# flackerlicht.net
KiCad netlist of a schematic drawn in EAGLE
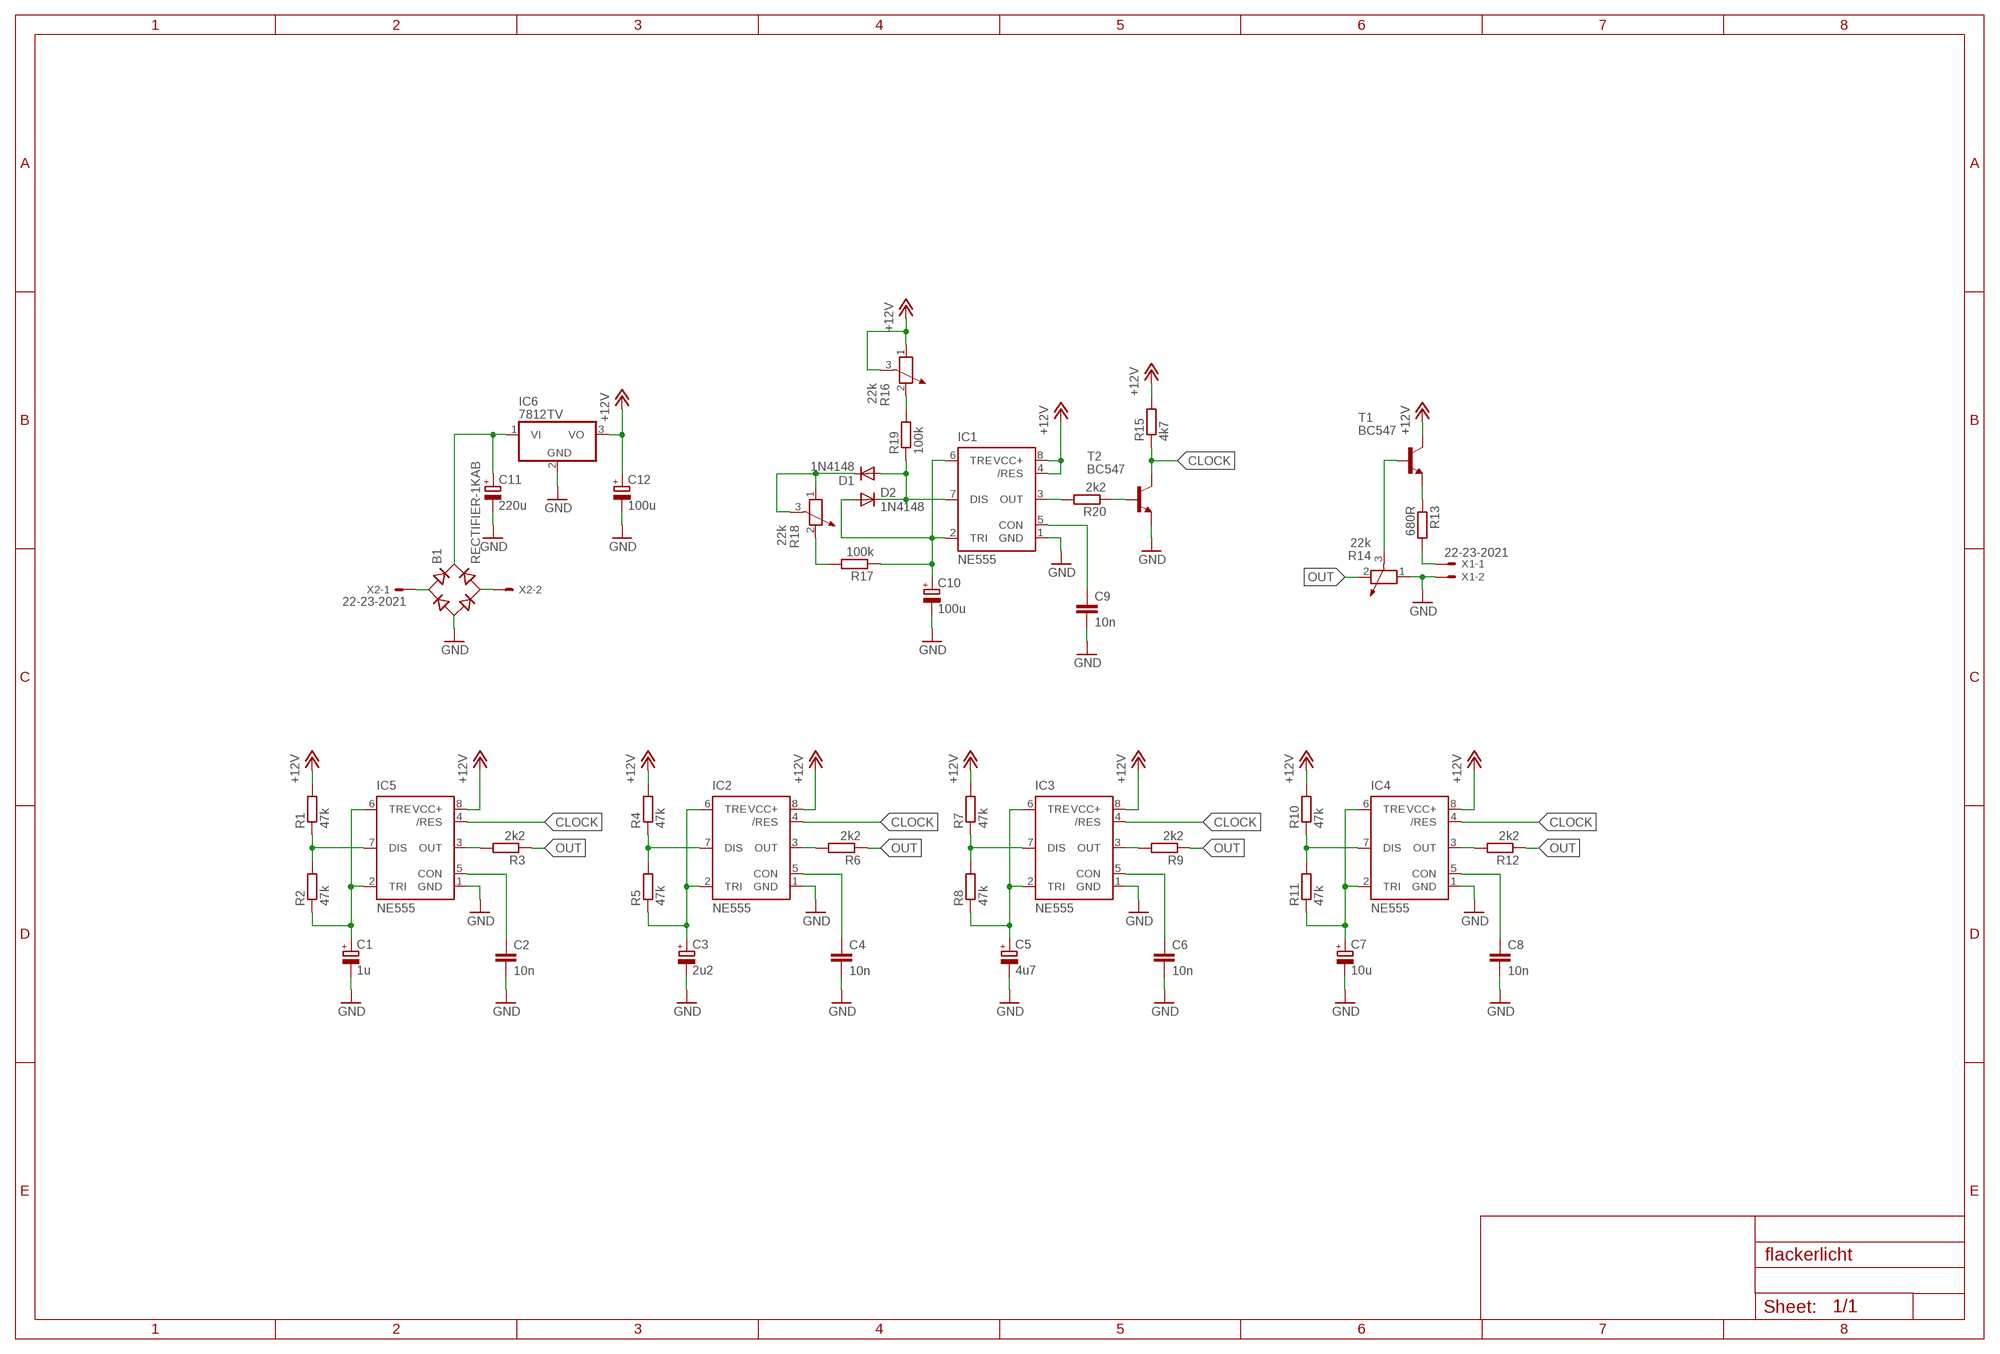
[diagram p0: schematic, sheet 1]

(export (version "E")
  (design (tool "Eeschema 10.0.6"))
  (components
    (comp (ref "B1")
      (value "RECTIFIER-1KAB")
      (footprint "eagle-import:1KAB")
      (libsource (lib "eagle-import") (part "RECTIFIER-1KAB"))
    )
    (comp (ref "C1")
      (value "1u")
      (footprint "eagle-import:E2,5-6")
      (libsource (lib "eagle-import") (part "CPOL-EUE2.5-6"))
    )
    (comp (ref "C2")
      (value "10n")
      (footprint "eagle-import:C050-035X075")
      (libsource (lib "eagle-import") (part "C-EU050-035X075"))
    )
    (comp (ref "C3")
      (value "2u2")
      (footprint "eagle-import:E2,5-6")
      (libsource (lib "eagle-import") (part "CPOL-EUE2.5-6"))
    )
    (comp (ref "C4")
      (value "10n")
      (footprint "eagle-import:C050-035X075")
      (libsource (lib "eagle-import") (part "C-EU050-035X075"))
    )
    (comp (ref "C5")
      (value "4u7")
      (footprint "eagle-import:E2,5-6")
      (libsource (lib "eagle-import") (part "CPOL-EUE2.5-6"))
    )
    (comp (ref "C6")
      (value "10n")
      (footprint "eagle-import:C050-035X075")
      (libsource (lib "eagle-import") (part "C-EU050-035X075"))
    )
    (comp (ref "C7")
      (value "10u")
      (footprint "eagle-import:E2,5-6")
      (libsource (lib "eagle-import") (part "CPOL-EUE2.5-6"))
    )
    (comp (ref "C8")
      (value "10n")
      (footprint "eagle-import:C050-035X075")
      (libsource (lib "eagle-import") (part "C-EU050-035X075"))
    )
    (comp (ref "C9")
      (value "10n")
      (footprint "eagle-import:C050-035X075")
      (libsource (lib "eagle-import") (part "C-EU050-035X075"))
    )
    (comp (ref "C10")
      (value "100u")
      (footprint "eagle-import:E3,5-8")
      (libsource (lib "eagle-import") (part "CPOL-EUE3.5-8"))
    )
    (comp (ref "C11")
      (value "220u")
      (footprint "eagle-import:E3,5-8")
      (libsource (lib "eagle-import") (part "CPOL-EUE3.5-8"))
    )
    (comp (ref "C12")
      (value "100u")
      (footprint "eagle-import:E3,5-8")
      (libsource (lib "eagle-import") (part "CPOL-EUE3.5-8"))
    )
    (comp (ref "D1")
      (value "1N4148")
      (footprint "eagle-import:DO35-10")
      (libsource (lib "eagle-import") (part "1N4148DO35-10"))
    )
    (comp (ref "D2")
      (value "1N4148")
      (footprint "eagle-import:DO35-10")
      (libsource (lib "eagle-import") (part "1N4148DO35-10"))
    )
    (comp (ref "IC1")
      (value "NE555")
      (footprint "eagle-import:DIL-08")
      (fields (field (name "MF") "Arrow Electronics") (field (name "MPN") "NE555N"))
      (libsource (lib "eagle-import") (part "NE555"))
    )
    (comp (ref "IC2")
      (value "NE555")
      (footprint "eagle-import:DIL-08")
      (fields (field (name "MF") "Arrow Electronics") (field (name "MPN") "NE555N"))
      (libsource (lib "eagle-import") (part "NE555"))
    )
    (comp (ref "IC3")
      (value "NE555")
      (footprint "eagle-import:DIL-08")
      (fields (field (name "MF") "Arrow Electronics") (field (name "MPN") "NE555N"))
      (libsource (lib "eagle-import") (part "NE555"))
    )
    (comp (ref "IC4")
      (value "NE555")
      (footprint "eagle-import:DIL-08")
      (fields (field (name "MF") "Arrow Electronics") (field (name "MPN") "NE555N"))
      (libsource (lib "eagle-import") (part "NE555"))
    )
    (comp (ref "IC5")
      (value "NE555")
      (footprint "eagle-import:DIL-08")
      (fields (field (name "MF") "Arrow Electronics") (field (name "MPN") "NE555N"))
      (libsource (lib "eagle-import") (part "NE555"))
    )
    (comp (ref "IC6")
      (value "7812TV")
      (footprint "eagle-import:TO220V")
      (libsource (lib "eagle-import") (part "78TV12"))
    )
    (comp (ref "R1")
      (value "47k")
      (footprint "eagle-import:0309_10")
      (libsource (lib "eagle-import") (part "R-EU_0309/10"))
    )
    (comp (ref "R2")
      (value "47k")
      (footprint "eagle-import:0309_10")
      (libsource (lib "eagle-import") (part "R-EU_0309/10"))
    )
    (comp (ref "R3")
      (value "2k2")
      (footprint "eagle-import:0309_10")
      (libsource (lib "eagle-import") (part "R-EU_0309/10"))
    )
    (comp (ref "R4")
      (value "47k")
      (footprint "eagle-import:0309_10")
      (libsource (lib "eagle-import") (part "R-EU_0309/10"))
    )
    (comp (ref "R5")
      (value "47k")
      (footprint "eagle-import:0309_10")
      (libsource (lib "eagle-import") (part "R-EU_0309/10"))
    )
    (comp (ref "R6")
      (value "2k2")
      (footprint "eagle-import:0309_10")
      (libsource (lib "eagle-import") (part "R-EU_0309/10"))
    )
    (comp (ref "R7")
      (value "47k")
      (footprint "eagle-import:0309_10")
      (libsource (lib "eagle-import") (part "R-EU_0309/10"))
    )
    (comp (ref "R8")
      (value "47k")
      (footprint "eagle-import:0309_10")
      (libsource (lib "eagle-import") (part "R-EU_0309/10"))
    )
    (comp (ref "R9")
      (value "2k2")
      (footprint "eagle-import:0309_10")
      (libsource (lib "eagle-import") (part "R-EU_0309/10"))
    )
    (comp (ref "R10")
      (value "47k")
      (footprint "eagle-import:0309_10")
      (libsource (lib "eagle-import") (part "R-EU_0309/10"))
    )
    (comp (ref "R11")
      (value "47k")
      (footprint "eagle-import:0309_10")
      (libsource (lib "eagle-import") (part "R-EU_0309/10"))
    )
    (comp (ref "R12")
      (value "2k2")
      (footprint "eagle-import:0309_10")
      (libsource (lib "eagle-import") (part "R-EU_0309/10"))
    )
    (comp (ref "R13")
      (value "680R")
      (footprint "eagle-import:0309_10")
      (libsource (lib "eagle-import") (part "R-EU_0309/10"))
    )
    (comp (ref "R14")
      (value "22k")
      (footprint "eagle-import:PT-10")
      (libsource (lib "eagle-import") (part "POTENTIOMETER_PT-10"))
    )
    (comp (ref "R15")
      (value "4k7")
      (footprint "eagle-import:0309_10")
      (libsource (lib "eagle-import") (part "R-EU_0309/10"))
    )
    (comp (ref "R16")
      (value "22k")
      (footprint "eagle-import:PT-10")
      (libsource (lib "eagle-import") (part "POTENTIOMETER_PT-10"))
    )
    (comp (ref "R17")
      (value "100k")
      (footprint "eagle-import:0309_10")
      (libsource (lib "eagle-import") (part "R-EU_0309/10"))
    )
    (comp (ref "R18")
      (value "22k")
      (footprint "eagle-import:PT-10")
      (libsource (lib "eagle-import") (part "POTENTIOMETER_PT-10"))
    )
    (comp (ref "R19")
      (value "100k")
      (footprint "eagle-import:0309_10")
      (libsource (lib "eagle-import") (part "R-EU_0309/10"))
    )
    (comp (ref "R20")
      (value "2k2")
      (footprint "eagle-import:0309_10")
      (libsource (lib "eagle-import") (part "R-EU_0309/10"))
    )
    (comp (ref "T1")
      (value "BC547")
      (footprint "eagle-import:TO92")
      (libsource (lib "eagle-import") (part "BC547"))
    )
    (comp (ref "T2")
      (value "BC547")
      (footprint "eagle-import:TO92")
      (libsource (lib "eagle-import") (part "BC547"))
    )
    (comp (ref "X1")
      (value "22-23-2021")
      (footprint "eagle-import:22-23-2021")
      (fields (field (name "MF") "MOLEX"))
      (libsource (lib "eagle-import") (part "22-23-2021"))
    )
    (comp (ref "X2")
      (value "22-23-2021")
      (footprint "eagle-import:22-23-2021")
      (fields
        (field (name "MF") "MOLEX")
        (field (name "MF_1") "MOLEX")
        (field (name "MPN") "22-23-2021")
        (field (name "OC_FARNELL") "1462926")
        (field (name "OC_NEWARK") "25C3832")
      )
      (libsource (lib "eagle-import") (part "22-23-2021"))
    )
  )
  (nets
    (net (code "1") (name "+12V") (class "Default")
      (node (ref "C12") (pin "+") (pinfunction "+_+") (pintype "passive"))
      (node (ref "IC1") (pin "4") (pinfunction "/RES_4") (pintype "input"))
      (node (ref "IC1") (pin "8") (pinfunction "VCC+_8") (pintype "power_in"))
      (node (ref "IC2") (pin "8") (pinfunction "VCC+_8") (pintype "power_in"))
      (node (ref "IC3") (pin "8") (pinfunction "VCC+_8") (pintype "power_in"))
      (node (ref "IC4") (pin "8") (pinfunction "VCC+_8") (pintype "power_in"))
      (node (ref "IC5") (pin "8") (pinfunction "VCC+_8") (pintype "power_in"))
      (node (ref "IC6") (pin "3") (pinfunction "VO_3") (pintype "passive"))
      (node (ref "R1") (pin "2") (pinfunction "2_2") (pintype "passive"))
      (node (ref "R10") (pin "2") (pinfunction "2_2") (pintype "passive"))
      (node (ref "R15") (pin "2") (pinfunction "2_2") (pintype "passive"))
      (node (ref "R16") (pin "1") (pinfunction "1_1") (pintype "passive"))
      (node (ref "R16") (pin "3") (pinfunction "3_3") (pintype "passive"))
      (node (ref "R4") (pin "2") (pinfunction "2_2") (pintype "passive"))
      (node (ref "R7") (pin "2") (pinfunction "2_2") (pintype "passive"))
      (node (ref "T1") (pin "3") (pinfunction "C_3") (pintype "passive"))
    )
    (net (code "2") (name "CLOCK") (class "Default")
      (node (ref "IC2") (pin "4") (pinfunction "/RES_4") (pintype "input"))
      (node (ref "IC3") (pin "4") (pinfunction "/RES_4") (pintype "input"))
      (node (ref "IC4") (pin "4") (pinfunction "/RES_4") (pintype "input"))
      (node (ref "IC5") (pin "4") (pinfunction "/RES_4") (pintype "input"))
      (node (ref "R15") (pin "1") (pinfunction "1_1") (pintype "passive"))
      (node (ref "T2") (pin "3") (pinfunction "C_3") (pintype "passive"))
    )
    (net (code "3") (name "GND") (class "Default")
      (node (ref "B1") (pin "-") (pinfunction "-_-") (pintype "passive"))
      (node (ref "C1") (pin "-") (pinfunction "-_-") (pintype "passive"))
      (node (ref "C10") (pin "-") (pinfunction "-_-") (pintype "passive"))
      (node (ref "C11") (pin "-") (pinfunction "-_-") (pintype "passive"))
      (node (ref "C12") (pin "-") (pinfunction "-_-") (pintype "passive"))
      (node (ref "C2") (pin "2") (pinfunction "2_2") (pintype "passive"))
      (node (ref "C3") (pin "-") (pinfunction "-_-") (pintype "passive"))
      (node (ref "C4") (pin "2") (pinfunction "2_2") (pintype "passive"))
      (node (ref "C5") (pin "-") (pinfunction "-_-") (pintype "passive"))
      (node (ref "C6") (pin "2") (pinfunction "2_2") (pintype "passive"))
      (node (ref "C7") (pin "-") (pinfunction "-_-") (pintype "passive"))
      (node (ref "C8") (pin "2") (pinfunction "2_2") (pintype "passive"))
      (node (ref "C9") (pin "2") (pinfunction "2_2") (pintype "passive"))
      (node (ref "IC1") (pin "1") (pinfunction "GND_1") (pintype "power_in"))
      (node (ref "IC2") (pin "1") (pinfunction "GND_1") (pintype "power_in"))
      (node (ref "IC3") (pin "1") (pinfunction "GND_1") (pintype "power_in"))
      (node (ref "IC4") (pin "1") (pinfunction "GND_1") (pintype "power_in"))
      (node (ref "IC5") (pin "1") (pinfunction "GND_1") (pintype "power_in"))
      (node (ref "IC6") (pin "2") (pinfunction "GND_2") (pintype "passive"))
      (node (ref "R14") (pin "1") (pinfunction "1_1") (pintype "passive"))
      (node (ref "T2") (pin "1") (pinfunction "E_1") (pintype "passive"))
      (node (ref "X1") (pin "2") (pinfunction "S_2") (pintype "passive"))
    )
    (net (code "4") (name "Net-(D1-PadC)") (class "Default")
      (node (ref "D1") (pin "C") (pinfunction "C_C") (pintype "passive"))
      (node (ref "R18") (pin "1") (pinfunction "1_1") (pintype "passive"))
      (node (ref "R18") (pin "3") (pinfunction "3_3") (pintype "passive"))
    )
    (net (code "5") (name "Net-(IC1-CON)") (class "Default")
      (node (ref "C9") (pin "1") (pinfunction "1_1") (pintype "passive"))
      (node (ref "IC1") (pin "5") (pinfunction "CON_5") (pintype "input"))
    )
    (net (code "6") (name "Net-(IC1-DIS)") (class "Default")
      (node (ref "D1") (pin "A") (pinfunction "A_A") (pintype "passive"))
      (node (ref "D2") (pin "C") (pinfunction "C_C") (pintype "passive"))
      (node (ref "IC1") (pin "7") (pinfunction "DIS_7") (pintype "input"))
      (node (ref "R19") (pin "1") (pinfunction "1_1") (pintype "passive"))
    )
    (net (code "7") (name "Net-(IC1-OUT)") (class "Default")
      (node (ref "IC1") (pin "3") (pinfunction "OUT_3") (pintype "output"))
      (node (ref "R20") (pin "2") (pinfunction "2_2") (pintype "passive"))
    )
    (net (code "8") (name "Net-(IC1-TRE)") (class "Default")
      (node (ref "C10") (pin "+") (pinfunction "+_+") (pintype "passive"))
      (node (ref "D2") (pin "A") (pinfunction "A_A") (pintype "passive"))
      (node (ref "IC1") (pin "2") (pinfunction "TRI_2") (pintype "input"))
      (node (ref "IC1") (pin "6") (pinfunction "TRE_6") (pintype "input"))
      (node (ref "R17") (pin "1") (pinfunction "1_1") (pintype "passive"))
    )
    (net (code "9") (name "Net-(IC2-CON)") (class "Default")
      (node (ref "C4") (pin "1") (pinfunction "1_1") (pintype "passive"))
      (node (ref "IC2") (pin "5") (pinfunction "CON_5") (pintype "input"))
    )
    (net (code "10") (name "Net-(IC2-DIS)") (class "Default")
      (node (ref "IC2") (pin "7") (pinfunction "DIS_7") (pintype "input"))
      (node (ref "R4") (pin "1") (pinfunction "1_1") (pintype "passive"))
      (node (ref "R5") (pin "2") (pinfunction "2_2") (pintype "passive"))
    )
    (net (code "11") (name "Net-(IC2-OUT)") (class "Default")
      (node (ref "IC2") (pin "3") (pinfunction "OUT_3") (pintype "output"))
      (node (ref "R6") (pin "2") (pinfunction "2_2") (pintype "passive"))
    )
    (net (code "12") (name "Net-(IC2-TRE)") (class "Default")
      (node (ref "C3") (pin "+") (pinfunction "+_+") (pintype "passive"))
      (node (ref "IC2") (pin "2") (pinfunction "TRI_2") (pintype "input"))
      (node (ref "IC2") (pin "6") (pinfunction "TRE_6") (pintype "input"))
      (node (ref "R5") (pin "1") (pinfunction "1_1") (pintype "passive"))
    )
    (net (code "13") (name "Net-(IC3-CON)") (class "Default")
      (node (ref "C6") (pin "1") (pinfunction "1_1") (pintype "passive"))
      (node (ref "IC3") (pin "5") (pinfunction "CON_5") (pintype "input"))
    )
    (net (code "14") (name "Net-(IC3-DIS)") (class "Default")
      (node (ref "IC3") (pin "7") (pinfunction "DIS_7") (pintype "input"))
      (node (ref "R7") (pin "1") (pinfunction "1_1") (pintype "passive"))
      (node (ref "R8") (pin "2") (pinfunction "2_2") (pintype "passive"))
    )
    (net (code "15") (name "Net-(IC3-OUT)") (class "Default")
      (node (ref "IC3") (pin "3") (pinfunction "OUT_3") (pintype "output"))
      (node (ref "R9") (pin "2") (pinfunction "2_2") (pintype "passive"))
    )
    (net (code "16") (name "Net-(IC3-TRE)") (class "Default")
      (node (ref "C5") (pin "+") (pinfunction "+_+") (pintype "passive"))
      (node (ref "IC3") (pin "2") (pinfunction "TRI_2") (pintype "input"))
      (node (ref "IC3") (pin "6") (pinfunction "TRE_6") (pintype "input"))
      (node (ref "R8") (pin "1") (pinfunction "1_1") (pintype "passive"))
    )
    (net (code "17") (name "Net-(IC4-CON)") (class "Default")
      (node (ref "C8") (pin "1") (pinfunction "1_1") (pintype "passive"))
      (node (ref "IC4") (pin "5") (pinfunction "CON_5") (pintype "input"))
    )
    (net (code "18") (name "Net-(IC4-DIS)") (class "Default")
      (node (ref "IC4") (pin "7") (pinfunction "DIS_7") (pintype "input"))
      (node (ref "R10") (pin "1") (pinfunction "1_1") (pintype "passive"))
      (node (ref "R11") (pin "2") (pinfunction "2_2") (pintype "passive"))
    )
    (net (code "19") (name "Net-(IC4-OUT)") (class "Default")
      (node (ref "IC4") (pin "3") (pinfunction "OUT_3") (pintype "output"))
      (node (ref "R12") (pin "2") (pinfunction "2_2") (pintype "passive"))
    )
    (net (code "20") (name "Net-(IC4-TRE)") (class "Default")
      (node (ref "C7") (pin "+") (pinfunction "+_+") (pintype "passive"))
      (node (ref "IC4") (pin "2") (pinfunction "TRI_2") (pintype "input"))
      (node (ref "IC4") (pin "6") (pinfunction "TRE_6") (pintype "input"))
      (node (ref "R11") (pin "1") (pinfunction "1_1") (pintype "passive"))
    )
    (net (code "21") (name "Net-(IC5-CON)") (class "Default")
      (node (ref "C2") (pin "1") (pinfunction "1_1") (pintype "passive"))
      (node (ref "IC5") (pin "5") (pinfunction "CON_5") (pintype "input"))
    )
    (net (code "22") (name "Net-(IC5-DIS)") (class "Default")
      (node (ref "IC5") (pin "7") (pinfunction "DIS_7") (pintype "input"))
      (node (ref "R1") (pin "1") (pinfunction "1_1") (pintype "passive"))
      (node (ref "R2") (pin "2") (pinfunction "2_2") (pintype "passive"))
    )
    (net (code "23") (name "Net-(IC5-OUT)") (class "Default")
      (node (ref "IC5") (pin "3") (pinfunction "OUT_3") (pintype "output"))
      (node (ref "R3") (pin "2") (pinfunction "2_2") (pintype "passive"))
    )
    (net (code "24") (name "Net-(IC5-TRE)") (class "Default")
      (node (ref "C1") (pin "+") (pinfunction "+_+") (pintype "passive"))
      (node (ref "IC5") (pin "2") (pinfunction "TRI_2") (pintype "input"))
      (node (ref "IC5") (pin "6") (pinfunction "TRE_6") (pintype "input"))
      (node (ref "R2") (pin "1") (pinfunction "1_1") (pintype "passive"))
    )
    (net (code "25") (name "Net-(IC6-VI)") (class "Default")
      (node (ref "B1") (pin "+") (pinfunction "+_+") (pintype "passive"))
      (node (ref "C11") (pin "+") (pinfunction "+_+") (pintype "passive"))
      (node (ref "IC6") (pin "1") (pinfunction "VI_1") (pintype "input"))
    )
    (net (code "26") (name "Net-(R16-Pad2)") (class "Default")
      (node (ref "R16") (pin "2") (pinfunction "2_2") (pintype "passive"))
      (node (ref "R19") (pin "2") (pinfunction "2_2") (pintype "passive"))
    )
    (net (code "27") (name "Net-(R17-Pad2)") (class "Default")
      (node (ref "R17") (pin "2") (pinfunction "2_2") (pintype "passive"))
      (node (ref "R18") (pin "2") (pinfunction "2_2") (pintype "passive"))
    )
    (net (code "28") (name "Net-(T1-B)") (class "Default")
      (node (ref "R14") (pin "3") (pinfunction "3_3") (pintype "passive"))
      (node (ref "T1") (pin "2") (pinfunction "B_2") (pintype "passive"))
    )
    (net (code "29") (name "Net-(T1-E)") (class "Default")
      (node (ref "R13") (pin "1") (pinfunction "1_1") (pintype "passive"))
      (node (ref "T1") (pin "1") (pinfunction "E_1") (pintype "passive"))
    )
    (net (code "30") (name "Net-(T2-B)") (class "Default")
      (node (ref "R20") (pin "1") (pinfunction "1_1") (pintype "passive"))
      (node (ref "T2") (pin "2") (pinfunction "B_2") (pintype "passive"))
    )
    (net (code "31") (name "Net-(X1A-S)") (class "Default")
      (node (ref "R13") (pin "2") (pinfunction "2_2") (pintype "passive"))
      (node (ref "X1") (pin "1") (pinfunction "S_1") (pintype "passive"))
    )
    (net (code "32") (name "Net-(X2A-S)") (class "Default")
      (node (ref "B1") (pin "AC1") (pinfunction "AC1_AC1") (pintype "passive"))
      (node (ref "X2") (pin "1") (pinfunction "S_1") (pintype "passive"))
    )
    (net (code "33") (name "Net-(X2B-S)") (class "Default")
      (node (ref "B1") (pin "AC2") (pinfunction "AC2_AC2") (pintype "passive"))
      (node (ref "X2") (pin "2") (pinfunction "S_2") (pintype "passive"))
    )
    (net (code "34") (name "OUT") (class "Default")
      (node (ref "R12") (pin "1") (pinfunction "1_1") (pintype "passive"))
      (node (ref "R14") (pin "2") (pinfunction "2_2") (pintype "passive"))
      (node (ref "R3") (pin "1") (pinfunction "1_1") (pintype "passive"))
      (node (ref "R6") (pin "1") (pinfunction "1_1") (pintype "passive"))
      (node (ref "R9") (pin "1") (pinfunction "1_1") (pintype "passive"))
    )
  )
)
